# untitled.net
KiCad netlist of a schematic drawn in EAGLE
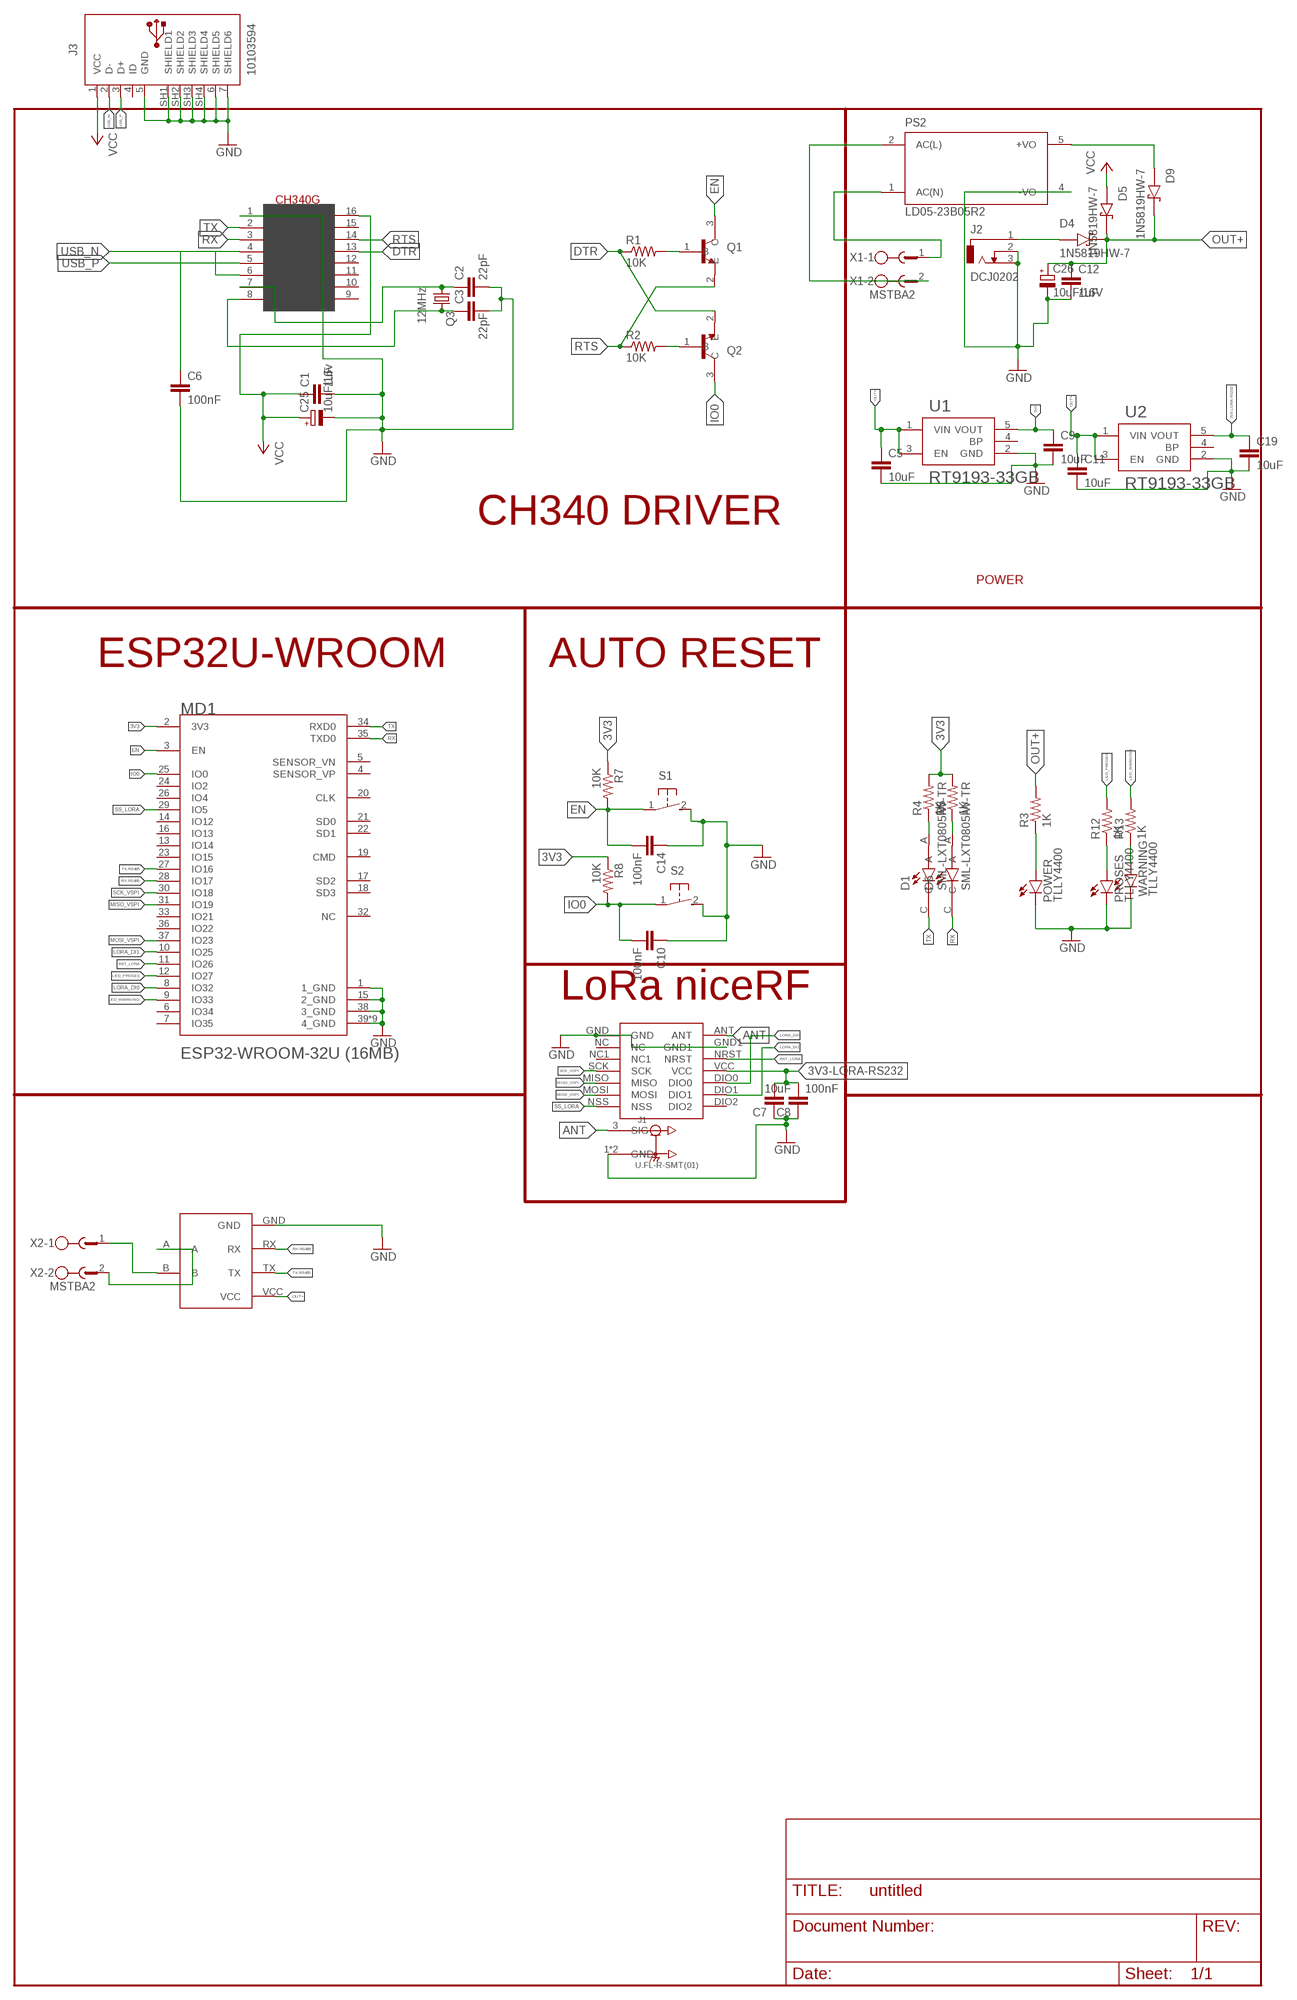
[diagram p0: schematic, sheet 1]

(export (version "E")
  (design (tool "Eeschema 10.0.6"))
  (components
    (comp (ref "C1")
      (value "1uF")
      (footprint "eagle-import:C0805K")
      (libsource (lib "eagle-import") (part "C-EUC0805K"))
    )
    (comp (ref "C2")
      (value "22pF")
      (footprint "eagle-import:C0805K")
      (libsource (lib "eagle-import") (part "C-EUC0805K"))
    )
    (comp (ref "C3")
      (value "22pF")
      (footprint "eagle-import:C0805K")
      (libsource (lib "eagle-import") (part "C-EUC0805K"))
    )
    (comp (ref "C5")
      (value "10uF")
      (footprint "eagle-import:C0805K")
      (libsource (lib "eagle-import") (part "C-EUC0805K"))
    )
    (comp (ref "C6")
      (value "100nF")
      (footprint "eagle-import:C0805K")
      (libsource (lib "eagle-import") (part "C-EUC0805K"))
    )
    (comp (ref "C7")
      (value "10uF")
      (footprint "eagle-import:C0805K")
      (libsource (lib "eagle-import") (part "C-EUC0805K"))
    )
    (comp (ref "C8")
      (value "100nF")
      (footprint "eagle-import:C0805K")
      (libsource (lib "eagle-import") (part "C-EUC0805K"))
    )
    (comp (ref "C9")
      (value "10uF")
      (footprint "eagle-import:C0805K")
      (libsource (lib "eagle-import") (part "C-EUC0805K"))
    )
    (comp (ref "C10")
      (value "100nF")
      (footprint "eagle-import:C0805K")
      (libsource (lib "eagle-import") (part "C-EUC0805K"))
    )
    (comp (ref "C11")
      (value "10uF")
      (footprint "eagle-import:C0805K")
      (libsource (lib "eagle-import") (part "C-EUC0805K"))
    )
    (comp (ref "C12")
      (value "1uF")
      (footprint "eagle-import:C0805K")
      (libsource (lib "eagle-import") (part "C-EUC0805K"))
    )
    (comp (ref "C14")
      (value "100nF")
      (footprint "eagle-import:C0805K")
      (libsource (lib "eagle-import") (part "C-EUC0805K"))
    )
    (comp (ref "C19")
      (value "10uF")
      (footprint "eagle-import:C0805K")
      (libsource (lib "eagle-import") (part "C-EUC0805K"))
    )
    (comp (ref "C25")
      (value "10uF/16v")
      (footprint "eagle-import:153CLV-0505")
      (libsource (lib "eagle-import") (part "CPOL-EU153CLV-0505"))
    )
    (comp (ref "C26")
      (value "10uF/16V")
      (footprint "eagle-import:153CLV-0505")
      (libsource (lib "eagle-import") (part "CPOL-EU153CLV-0505"))
    )
    (comp (ref "D1")
      (value "SML-LXT0805IW-TR")
      (footprint "eagle-import:LEDC2012X120N")
      (fields (field (name "MF") "Lumex Opto/Components"))
      (libsource (lib "eagle-import") (part "SML-LXT0805IW-TR"))
    )
    (comp (ref "D4")
      (value "1N5819HW-7")
      (footprint "eagle-import:SOD3715X145N")
      (fields (field (name "MF") "Diodes Inc."))
      (libsource (lib "eagle-import") (part "1N5819HW-7"))
    )
    (comp (ref "D5")
      (value "1N5819HW-7")
      (footprint "eagle-import:SOD3715X145N")
      (fields (field (name "MF") "Diodes Inc."))
      (libsource (lib "eagle-import") (part "1N5819HW-7"))
    )
    (comp (ref "D6")
      (value "SML-LXT0805IW-TR")
      (footprint "eagle-import:LEDC2012X120N")
      (fields (field (name "MF") "Lumex Opto/Components"))
      (libsource (lib "eagle-import") (part "SML-LXT0805IW-TR"))
    )
    (comp (ref "D9")
      (value "1N5819HW-7")
      (footprint "eagle-import:SOD3715X145N")
      (fields (field (name "MF") "Diodes Inc."))
      (libsource (lib "eagle-import") (part "1N5819HW-7"))
    )
    (comp (ref "J1")
      (value "U.FL-R-SMT(01)")
      (footprint "eagle-import:HRS_U.FL-R-SMT(01)")
      (fields (field (name "MF") "Hirose"))
      (libsource (lib "eagle-import") (part "U.FL-R-SMT(01)"))
    )
    (comp (ref "J2")
      (value "DCJ0202")
      (footprint "eagle-import:DCJ0202")
      (libsource (lib "eagle-import") (part "DCJ0202"))
    )
    (comp (ref "J3")
      (value "10103594")
      (footprint "eagle-import:10103594")
      (fields (field (name "MANUFACTURER") "Amphenol ICC (FCI)") (field (name "MPN") "10103594-0001LF"))
      (libsource (lib "eagle-import") (part "10103594"))
    )
    (comp (ref "LORA-NICERF-V1")
      (value "LORA-NICERF-V2")
      (footprint "eagle-import:LORA-NICERF-V2")
      (libsource (lib "eagle-import") (part "LORA-NICERF-V2"))
    )
    (comp (ref "MD1")
      (value "ESPRESSIF_SYSTEMS_ESP32-WROOM-32U_16MBESPRESSIF_SYSTEMS_ESP32-WROOM-32U_16MB_0_0")
      (footprint "eagle-import:ESPRESSIF_SYSTEMS_ESP32-WROOM-32U_16MB_0")
      (fields
        (field (name "DIGIKEY_PART_NUMBER") "1904-1028-1-ND")
        (field (name "MF") "Espressif Systems")
        (field (name "MOUSER_PART_NUMBER") "356-ES32WROOM32U16MB")
      )
      (libsource (lib "eagle-import") (part "ESPRESSIF_SYSTEMS_ESP32-WROOM-32U_16MBESPRESSIF_SYSTEMS_ESP32-WROOM-32U_16MB_0_0"))
    )
    (comp (ref "POWER")
      (value "TLLY4400")
      (footprint "eagle-import:LED3MM")
      (fields (field (name "MF") "VISHAY SEMICONDUCTOR"))
      (libsource (lib "eagle-import") (part "TLLY4400"))
    )
    (comp (ref "PROSES")
      (value "TLLY4400")
      (footprint "eagle-import:LED3MM")
      (fields (field (name "MF") "VISHAY SEMICONDUCTOR"))
      (libsource (lib "eagle-import") (part "TLLY4400"))
    )
    (comp (ref "PS2")
      (value "LD05-23B05R2")
      (footprint "eagle-import:CONV_LD05-23B05R2")
      (fields (field (name "MF") "Mornsun America, LLC"))
      (libsource (lib "eagle-import") (part "LD05-23B05R2"))
    )
    (comp (ref "Q1")
      (value "MMBT3904")
      (footprint "eagle-import:SOT95P240X120-3N")
      (fields (field (name "MF") "STMicroelectronics"))
      (libsource (lib "eagle-import") (part "MMBT3904"))
    )
    (comp (ref "Q2")
      (value "MMBT3904")
      (footprint "eagle-import:SOT95P240X120-3N")
      (fields (field (name "MF") "STMicroelectronics"))
      (libsource (lib "eagle-import") (part "MMBT3904"))
    )
    (comp (ref "Q3")
      (value "12MHz")
      (footprint "eagle-import:SM49")
      (libsource (lib "eagle-import") (part "CRYSTALSM49"))
    )
    (comp (ref "R1")
      (value "10K")
      (footprint "eagle-import:M0805")
      (libsource (lib "eagle-import") (part "R-US_M0805"))
    )
    (comp (ref "R2")
      (value "10K")
      (footprint "eagle-import:M0805")
      (libsource (lib "eagle-import") (part "R-US_M0805"))
    )
    (comp (ref "R3")
      (value "1K")
      (footprint "eagle-import:M0805")
      (libsource (lib "eagle-import") (part "R-US_M0805"))
    )
    (comp (ref "R4")
      (value "1K")
      (footprint "eagle-import:M0805")
      (libsource (lib "eagle-import") (part "R-US_M0805"))
    )
    (comp (ref "R5")
      (value "1K")
      (footprint "eagle-import:M0805")
      (libsource (lib "eagle-import") (part "R-US_M0805"))
    )
    (comp (ref "R7")
      (value "10K")
      (footprint "eagle-import:M0805")
      (libsource (lib "eagle-import") (part "R-US_M0805"))
    )
    (comp (ref "R8")
      (value "10K")
      (footprint "eagle-import:M0805")
      (libsource (lib "eagle-import") (part "R-US_M0805"))
    )
    (comp (ref "R12")
      (value "1K")
      (footprint "eagle-import:M0805")
      (libsource (lib "eagle-import") (part "R-US_M0805"))
    )
    (comp (ref "R13")
      (value "1K")
      (footprint "eagle-import:M0805")
      (libsource (lib "eagle-import") (part "R-US_M0805"))
    )
    (comp (ref "S1")
      (value "31-XX")
      (footprint "eagle-import:B3F-31XX")
      (fields (field (name "MPN") "B3F-3100"))
      (libsource (lib "eagle-import") (part "31-XX"))
    )
    (comp (ref "S2")
      (value "31-XX")
      (footprint "eagle-import:B3F-31XX")
      (fields (field (name "MPN") "B3F-3100"))
      (libsource (lib "eagle-import") (part "31-XX"))
    )
    (comp (ref "TTL-RS1")
      (value "TTL-RS485")
      (footprint "eagle-import:TTL-RS485")
      (libsource (lib "eagle-import") (part "TTL-RS485"))
    )
    (comp (ref "U$2")
      (value "CH340G")
      (footprint "eagle-import:SOIC16")
      (libsource (lib "eagle-import") (part "CH340G"))
    )
    (comp (ref "U1")
      (value "RT9193-33GB")
      (footprint "eagle-import:SOT94P279X129-5N")
      (fields (field (name "MF") "Richtek USA Inc."))
      (libsource (lib "eagle-import") (part "RT9193-33GB"))
    )
    (comp (ref "U2")
      (value "RT9193-33GB")
      (footprint "eagle-import:SOT94P279X129-5N")
      (fields (field (name "MF") "Richtek USA Inc."))
      (libsource (lib "eagle-import") (part "RT9193-33GB"))
    )
    (comp (ref "WARNING")
      (value "TLLY4400")
      (footprint "eagle-import:LED3MM")
      (fields (field (name "MF") "VISHAY SEMICONDUCTOR"))
      (libsource (lib "eagle-import") (part "TLLY4400"))
    )
    (comp (ref "X1")
      (value "MSTBA2")
      (footprint "eagle-import:MSTBA2")
      (fields (field (name "MF") "FARNELL") (field (name "MPN") "1757242"))
      (libsource (lib "eagle-import") (part "MSTBA2"))
    )
    (comp (ref "X2")
      (value "MSTBA2")
      (footprint "eagle-import:MSTBA2")
      (fields (field (name "MF") "FARNELL") (field (name "MPN") "1757242"))
      (libsource (lib "eagle-import") (part "MSTBA2"))
    )
  )
  (nets
    (net (code "1") (name "3V3") (class "Default")
      (node (ref "C9") (pin "1") (pinfunction "1_1") (pintype "passive"))
      (node (ref "MD1") (pin "2") (pinfunction "3V3_2") (pintype "power_in"))
      (node (ref "R4") (pin "2") (pinfunction "2_2") (pintype "passive"))
      (node (ref "R5") (pin "2") (pinfunction "2_2") (pintype "passive"))
      (node (ref "R7") (pin "1") (pinfunction "1_1") (pintype "passive"))
      (node (ref "R8") (pin "1") (pinfunction "1_1") (pintype "passive"))
      (node (ref "U1") (pin "5") (pinfunction "VOUT_5") (pintype "output"))
    )
    (net (code "2") (name "3V3-LORA-RS232") (class "Default")
      (node (ref "C19") (pin "1") (pinfunction "1_1") (pintype "passive"))
      (node (ref "C7") (pin "2") (pinfunction "2_2") (pintype "passive"))
      (node (ref "C8") (pin "2") (pinfunction "2_2") (pintype "passive"))
      (node (ref "LORA-NICERF-V1") (pin "VCC") (pinfunction "VCC_VCC") (pintype "bidirectional"))
      (node (ref "U2") (pin "5") (pinfunction "VOUT_5") (pintype "output"))
    )
    (net (code "3") (name "ANT") (class "Default")
      (node (ref "J1") (pin "3") (pinfunction "SIG_3") (pintype "passive"))
      (node (ref "LORA-NICERF-V1") (pin "ANT") (pinfunction "ANT_ANT") (pintype "bidirectional"))
    )
    (net (code "4") (name "DTR") (class "Default")
      (node (ref "Q2") (pin "2") (pinfunction "E_2") (pintype "passive"))
      (node (ref "R1") (pin "1") (pinfunction "1_1") (pintype "passive"))
      (node (ref "U$2") (pin "13") (pinfunction "DTR_13") (pintype "bidirectional"))
    )
    (net (code "5") (name "EN") (class "Default")
      (node (ref "C14") (pin "2") (pinfunction "2_2") (pintype "passive"))
      (node (ref "MD1") (pin "3") (pinfunction "EN_3") (pintype "input"))
      (node (ref "Q1") (pin "3") (pinfunction "C_3") (pintype "passive"))
      (node (ref "R7") (pin "2") (pinfunction "2_2") (pintype "passive"))
      (node (ref "S1") (pin "1") (pinfunction "P_1") (pintype "passive"))
    )
    (net (code "6") (name "GND") (class "Default")
      (node (ref "C1") (pin "2") (pinfunction "2_2") (pintype "passive"))
      (node (ref "C10") (pin "1") (pinfunction "1_1") (pintype "passive"))
      (node (ref "C11") (pin "2") (pinfunction "2_2") (pintype "passive"))
      (node (ref "C12") (pin "2") (pinfunction "2_2") (pintype "passive"))
      (node (ref "C14") (pin "1") (pinfunction "1_1") (pintype "passive"))
      (node (ref "C19") (pin "2") (pinfunction "2_2") (pintype "passive"))
      (node (ref "C2") (pin "2") (pinfunction "2_2") (pintype "passive"))
      (node (ref "C25") (pin "-") (pinfunction "-_-") (pintype "passive"))
      (node (ref "C26") (pin "-") (pinfunction "-_-") (pintype "passive"))
      (node (ref "C3") (pin "2") (pinfunction "2_2") (pintype "passive"))
      (node (ref "C5") (pin "2") (pinfunction "2_2") (pintype "passive"))
      (node (ref "C6") (pin "2") (pinfunction "2_2") (pintype "passive"))
      (node (ref "C7") (pin "1") (pinfunction "1_1") (pintype "passive"))
      (node (ref "C8") (pin "1") (pinfunction "1_1") (pintype "passive"))
      (node (ref "C9") (pin "2") (pinfunction "2_2") (pintype "passive"))
      (node (ref "J1") (pin "1") (pinfunction "GND_1") (pintype "passive"))
      (node (ref "J1") (pin "2") (pinfunction "GND_2") (pintype "passive"))
      (node (ref "J2") (pin "2") (pinfunction "2_2") (pintype "passive"))
      (node (ref "J2") (pin "3") (pinfunction "3_3") (pintype "passive"))
      (node (ref "J3") (pin "5") (pinfunction "GND_5") (pintype "power_in"))
      (node (ref "J3") (pin "6") (pinfunction "SHIELD5_6") (pintype "power_in"))
      (node (ref "J3") (pin "7") (pinfunction "SHIELD6_7") (pintype "power_in"))
      (node (ref "J3") (pin "SH1") (pinfunction "SHIELD1_SH1") (pintype "power_in"))
      (node (ref "J3") (pin "SH2") (pinfunction "SHIELD2_SH2") (pintype "power_in"))
      (node (ref "J3") (pin "SH3") (pinfunction "SHIELD3_SH3") (pintype "power_in"))
      (node (ref "J3") (pin "SH4") (pinfunction "SHIELD4_SH4") (pintype "power_in"))
      (node (ref "LORA-NICERF-V1") (pin "GND") (pinfunction "GND_GND") (pintype "bidirectional"))
      (node (ref "LORA-NICERF-V1") (pin "GND1") (pinfunction "GND1_GND1") (pintype "bidirectional"))
      (node (ref "MD1") (pin "1") (pinfunction "1_GND_1") (pintype "power_in"))
      (node (ref "MD1") (pin "15") (pinfunction "2_GND_15") (pintype "power_in"))
      (node (ref "MD1") (pin "38") (pinfunction "3_GND_38") (pintype "power_in"))
      (node (ref "MD1") (pin "39") (pinfunction "4_GND_39") (pintype "power_in"))
      (node (ref "MD1") (pin "39-2") (pinfunction "4_GND_39-2") (pintype "power_in"))
      (node (ref "MD1") (pin "39-3") (pinfunction "4_GND_39-3") (pintype "power_in"))
      (node (ref "MD1") (pin "39-4") (pinfunction "4_GND_39-4") (pintype "power_in"))
      (node (ref "MD1") (pin "39-5") (pinfunction "4_GND_39-5") (pintype "power_in"))
      (node (ref "MD1") (pin "39-6") (pinfunction "4_GND_39-6") (pintype "power_in"))
      (node (ref "MD1") (pin "39-7") (pinfunction "4_GND_39-7") (pintype "power_in"))
      (node (ref "MD1") (pin "39-8") (pinfunction "4_GND_39-8") (pintype "power_in"))
      (node (ref "MD1") (pin "39-9") (pinfunction "4_GND_39-9") (pintype "power_in"))
      (node (ref "POWER") (pin "K") (pinfunction "C_K") (pintype "passive"))
      (node (ref "PROSES") (pin "K") (pinfunction "C_K") (pintype "passive"))
      (node (ref "PS2") (pin "4") (pinfunction "-VO_4") (pintype "output"))
      (node (ref "S1") (pin "2") (pinfunction "S_2") (pintype "passive"))
      (node (ref "S2") (pin "2") (pinfunction "S_2") (pintype "passive"))
      (node (ref "TTL-RS1") (pin "GND") (pinfunction "GND_GND") (pintype "bidirectional"))
      (node (ref "U$2") (pin "1") (pinfunction "GND_1") (pintype "bidirectional"))
      (node (ref "U1") (pin "2") (pinfunction "GND_2") (pintype "power_in"))
      (node (ref "U2") (pin "2") (pinfunction "GND_2") (pintype "power_in"))
      (node (ref "WARNING") (pin "K") (pinfunction "C_K") (pintype "passive"))
    )
    (net (code "7") (name "IO0") (class "Default")
      (node (ref "C10") (pin "2") (pinfunction "2_2") (pintype "passive"))
      (node (ref "MD1") (pin "25") (pinfunction "IO0_25") (pintype "bidirectional"))
      (node (ref "Q2") (pin "3") (pinfunction "C_3") (pintype "passive"))
      (node (ref "R8") (pin "2") (pinfunction "2_2") (pintype "passive"))
      (node (ref "S2") (pin "1") (pinfunction "P_1") (pintype "passive"))
    )
    (net (code "8") (name "LED_PROSES") (class "Default")
      (node (ref "MD1") (pin "12") (pinfunction "IO27_12") (pintype "bidirectional"))
      (node (ref "R12") (pin "2") (pinfunction "2_2") (pintype "passive"))
    )
    (net (code "9") (name "LED_WARNING") (class "Default")
      (node (ref "MD1") (pin "9") (pinfunction "IO33_9") (pintype "bidirectional"))
      (node (ref "R13") (pin "2") (pinfunction "2_2") (pintype "passive"))
    )
    (net (code "10") (name "LORA_DI0") (class "Default")
      (node (ref "LORA-NICERF-V1") (pin "DIO0") (pinfunction "DIO0_DIO0") (pintype "bidirectional"))
      (node (ref "MD1") (pin "8") (pinfunction "IO32_8") (pintype "bidirectional"))
    )
    (net (code "11") (name "LORA_DI1") (class "Default")
      (node (ref "LORA-NICERF-V1") (pin "DIO1") (pinfunction "DIO1_DIO1") (pintype "bidirectional"))
      (node (ref "MD1") (pin "10") (pinfunction "IO25_10") (pintype "bidirectional"))
    )
    (net (code "12") (name "MISO_VSPI") (class "Default")
      (node (ref "LORA-NICERF-V1") (pin "MISO") (pinfunction "MISO_MISO") (pintype "bidirectional"))
      (node (ref "MD1") (pin "31") (pinfunction "IO19_31") (pintype "bidirectional"))
    )
    (net (code "13") (name "MOSI_VSPI") (class "Default")
      (node (ref "LORA-NICERF-V1") (pin "MOSI") (pinfunction "MOSI_MOSI") (pintype "bidirectional"))
      (node (ref "MD1") (pin "37") (pinfunction "IO23_37") (pintype "bidirectional"))
    )
    (net (code "14") (name "Net-(D1-PadA)") (class "Default")
      (node (ref "D1") (pin "A") (pinfunction "A_A") (pintype "passive"))
      (node (ref "R4") (pin "1") (pinfunction "1_1") (pintype "passive"))
    )
    (net (code "15") (name "Net-(D4-PadA)") (class "Default")
      (node (ref "D4") (pin "A") (pinfunction "A_A") (pintype "passive"))
      (node (ref "J2") (pin "1") (pinfunction "1_1") (pintype "passive"))
    )
    (net (code "16") (name "Net-(D6-PadA)") (class "Default")
      (node (ref "D6") (pin "A") (pinfunction "A_A") (pintype "passive"))
      (node (ref "R5") (pin "1") (pinfunction "1_1") (pintype "passive"))
    )
    (net (code "17") (name "Net-(POWER-PadA)") (class "Default")
      (node (ref "POWER") (pin "A") (pinfunction "A_A") (pintype "passive"))
      (node (ref "R3") (pin "1") (pinfunction "1_1") (pintype "passive"))
    )
    (net (code "18") (name "Net-(PROSES-PadA)") (class "Default")
      (node (ref "PROSES") (pin "A") (pinfunction "A_A") (pintype "passive"))
      (node (ref "R12") (pin "1") (pinfunction "1_1") (pintype "passive"))
    )
    (net (code "19") (name "Net-(PS2-+VO)") (class "Default")
      (node (ref "D9") (pin "A") (pinfunction "A_A") (pintype "passive"))
      (node (ref "PS2") (pin "5") (pinfunction "+VO_5") (pintype "output"))
    )
    (net (code "20") (name "Net-(PS2-AC(L))") (class "Default")
      (node (ref "PS2") (pin "2") (pinfunction "AC(L)_2") (pintype "input"))
      (node (ref "X1") (pin "2") (pinfunction "1_2") (pintype "passive"))
    )
    (net (code "21") (name "Net-(PS2-AC(N))") (class "Default")
      (node (ref "PS2") (pin "1") (pinfunction "AC(N)_1") (pintype "input"))
      (node (ref "X1") (pin "1") (pinfunction "1_1") (pintype "passive"))
    )
    (net (code "22") (name "Net-(Q1-B)") (class "Default")
      (node (ref "Q1") (pin "1") (pinfunction "B_1") (pintype "passive"))
      (node (ref "R1") (pin "2") (pinfunction "2_2") (pintype "passive"))
    )
    (net (code "23") (name "Net-(Q2-B)") (class "Default")
      (node (ref "Q2") (pin "1") (pinfunction "B_1") (pintype "passive"))
      (node (ref "R2") (pin "2") (pinfunction "2_2") (pintype "passive"))
    )
    (net (code "24") (name "Net-(R13-Pad1)") (class "Default")
      (node (ref "R13") (pin "1") (pinfunction "1_1") (pintype "passive"))
      (node (ref "WARNING") (pin "A") (pinfunction "A_A") (pintype "passive"))
    )
    (net (code "25") (name "Net-(TTL-RS1-PadB)") (class "Default")
      (node (ref "TTL-RS1") (pin "B") (pinfunction "B_B") (pintype "bidirectional"))
      (node (ref "X2") (pin "1") (pinfunction "1_1") (pintype "passive"))
    )
    (net (code "26") (name "Net-(U$2-V3)") (class "Default")
      (node (ref "C6") (pin "1") (pinfunction "1_1") (pintype "passive"))
      (node (ref "U$2") (pin "4") (pinfunction "V3_4") (pintype "bidirectional"))
    )
    (net (code "27") (name "Net-(U$2-XI)") (class "Default")
      (node (ref "C2") (pin "1") (pinfunction "1_1") (pintype "passive"))
      (node (ref "Q3") (pin "1") (pinfunction "1_1") (pintype "passive"))
      (node (ref "U$2") (pin "7") (pinfunction "XI_7") (pintype "bidirectional"))
    )
    (net (code "28") (name "Net-(U$2-XO)") (class "Default")
      (node (ref "C3") (pin "1") (pinfunction "1_1") (pintype "passive"))
      (node (ref "Q3") (pin "2") (pinfunction "2_2") (pintype "passive"))
      (node (ref "U$2") (pin "8") (pinfunction "XO_8") (pintype "bidirectional"))
    )
    (net (code "29") (name "Net-(X2B-1)") (class "Default")
      (node (ref "TTL-RS1") (pin "A") (pinfunction "A_A") (pintype "bidirectional"))
      (node (ref "X2") (pin "2") (pinfunction "1_2") (pintype "passive"))
    )
    (net (code "30") (name "OUT+") (class "Default")
      (node (ref "C11") (pin "1") (pinfunction "1_1") (pintype "passive"))
      (node (ref "C12") (pin "1") (pinfunction "1_1") (pintype "passive"))
      (node (ref "C26") (pin "+") (pinfunction "+_+") (pintype "passive"))
      (node (ref "C5") (pin "1") (pinfunction "1_1") (pintype "passive"))
      (node (ref "D4") (pin "C") (pinfunction "K_C") (pintype "passive"))
      (node (ref "D5") (pin "C") (pinfunction "K_C") (pintype "passive"))
      (node (ref "D9") (pin "C") (pinfunction "K_C") (pintype "passive"))
      (node (ref "R3") (pin "2") (pinfunction "2_2") (pintype "passive"))
      (node (ref "TTL-RS1") (pin "VCC") (pinfunction "VCC_VCC") (pintype "bidirectional"))
      (node (ref "U1") (pin "1") (pinfunction "VIN_1") (pintype "input"))
      (node (ref "U1") (pin "3") (pinfunction "EN_3") (pintype "input"))
      (node (ref "U2") (pin "1") (pinfunction "VIN_1") (pintype "input"))
      (node (ref "U2") (pin "3") (pinfunction "EN_3") (pintype "input"))
    )
    (net (code "31") (name "RST_LORA") (class "Default")
      (node (ref "LORA-NICERF-V1") (pin "NRST") (pinfunction "NRST_NRST") (pintype "bidirectional"))
      (node (ref "MD1") (pin "11") (pinfunction "IO26_11") (pintype "bidirectional"))
    )
    (net (code "32") (name "RTS") (class "Default")
      (node (ref "Q1") (pin "2") (pinfunction "E_2") (pintype "passive"))
      (node (ref "R2") (pin "1") (pinfunction "1_1") (pintype "passive"))
      (node (ref "U$2") (pin "14") (pinfunction "RTS_14") (pintype "bidirectional"))
    )
    (net (code "33") (name "RX") (class "Default")
      (node (ref "D6") (pin "C") (pinfunction "C_C") (pintype "passive"))
      (node (ref "MD1") (pin "35") (pinfunction "TXD0_35") (pintype "bidirectional"))
      (node (ref "U$2") (pin "3") (pinfunction "RX_3") (pintype "bidirectional"))
    )
    (net (code "34") (name "RX-RS485") (class "Default")
      (node (ref "MD1") (pin "28") (pinfunction "IO17_28") (pintype "bidirectional"))
      (node (ref "TTL-RS1") (pin "RX") (pinfunction "RX_RX") (pintype "bidirectional"))
    )
    (net (code "35") (name "SCK_VSPI") (class "Default")
      (node (ref "LORA-NICERF-V1") (pin "SCK") (pinfunction "SCK_SCK") (pintype "bidirectional"))
      (node (ref "MD1") (pin "30") (pinfunction "IO18_30") (pintype "bidirectional"))
    )
    (net (code "36") (name "SS_LORA") (class "Default")
      (node (ref "LORA-NICERF-V1") (pin "NSS") (pinfunction "NSS_NSS") (pintype "bidirectional"))
      (node (ref "MD1") (pin "29") (pinfunction "IO5_29") (pintype "bidirectional"))
    )
    (net (code "37") (name "TX") (class "Default")
      (node (ref "D1") (pin "C") (pinfunction "C_C") (pintype "passive"))
      (node (ref "MD1") (pin "34") (pinfunction "RXD0_34") (pintype "bidirectional"))
      (node (ref "U$2") (pin "2") (pinfunction "TX_2") (pintype "bidirectional"))
    )
    (net (code "38") (name "TX-RS485") (class "Default")
      (node (ref "MD1") (pin "27") (pinfunction "IO16_27") (pintype "bidirectional"))
      (node (ref "TTL-RS1") (pin "TX") (pinfunction "TX_TX") (pintype "bidirectional"))
    )
    (net (code "39") (name "USB_N") (class "Default")
      (node (ref "J3") (pin "2") (pinfunction "D-_2") (pintype "bidirectional"))
      (node (ref "U$2") (pin "6") (pinfunction "D-_6") (pintype "bidirectional"))
    )
    (net (code "40") (name "USB_P") (class "Default")
      (node (ref "J3") (pin "3") (pinfunction "D+_3") (pintype "bidirectional"))
      (node (ref "U$2") (pin "5") (pinfunction "D+_5") (pintype "bidirectional"))
    )
    (net (code "41") (name "VCC") (class "Default")
      (node (ref "C1") (pin "1") (pinfunction "1_1") (pintype "passive"))
      (node (ref "C25") (pin "+") (pinfunction "+_+") (pintype "passive"))
      (node (ref "D5") (pin "A") (pinfunction "A_A") (pintype "passive"))
      (node (ref "J3") (pin "1") (pinfunction "VCC_1") (pintype "power_in"))
      (node (ref "U$2") (pin "16") (pinfunction "VCC_16") (pintype "bidirectional"))
    )
    (net (code "42") (name "unconnected-(J3-ID-Pad4)") (class "Default")
      (node (ref "J3") (pin "4") (pinfunction "ID_4") (pintype "bidirectional"))
    )
    (net (code "43") (name "unconnected-(LORA-NICERF-V1-PadDIO2)") (class "Default")
      (node (ref "LORA-NICERF-V1") (pin "DIO2") (pinfunction "DIO2_DIO2") (pintype "bidirectional"))
    )
    (net (code "44") (name "unconnected-(LORA-NICERF-V1-PadNC)") (class "Default")
      (node (ref "LORA-NICERF-V1") (pin "NC") (pinfunction "NC_NC") (pintype "bidirectional"))
    )
    (net (code "45") (name "unconnected-(LORA-NICERF-V1-PadNC1)") (class "Default")
      (node (ref "LORA-NICERF-V1") (pin "NC1") (pinfunction "NC1_NC1") (pintype "bidirectional"))
    )
    (net (code "46") (name "unconnected-(MD1-CLK-Pad20)") (class "Default")
      (node (ref "MD1") (pin "20") (pinfunction "CLK_20") (pintype "bidirectional"))
    )
    (net (code "47") (name "unconnected-(MD1-CMD-Pad19)") (class "Default")
      (node (ref "MD1") (pin "19") (pinfunction "CMD_19") (pintype "bidirectional"))
    )
    (net (code "48") (name "unconnected-(MD1-IO2-Pad24)") (class "Default")
      (node (ref "MD1") (pin "24") (pinfunction "IO2_24") (pintype "bidirectional"))
    )
    (net (code "49") (name "unconnected-(MD1-IO4-Pad26)") (class "Default")
      (node (ref "MD1") (pin "26") (pinfunction "IO4_26") (pintype "bidirectional"))
    )
    (net (code "50") (name "unconnected-(MD1-IO12-Pad14)") (class "Default")
      (node (ref "MD1") (pin "14") (pinfunction "IO12_14") (pintype "bidirectional"))
    )
    (net (code "51") (name "unconnected-(MD1-IO13-Pad16)") (class "Default")
      (node (ref "MD1") (pin "16") (pinfunction "IO13_16") (pintype "bidirectional"))
    )
    (net (code "52") (name "unconnected-(MD1-IO14-Pad13)") (class "Default")
      (node (ref "MD1") (pin "13") (pinfunction "IO14_13") (pintype "bidirectional"))
    )
    (net (code "53") (name "unconnected-(MD1-IO15-Pad23)") (class "Default")
      (node (ref "MD1") (pin "23") (pinfunction "IO15_23") (pintype "bidirectional"))
    )
    (net (code "54") (name "unconnected-(MD1-IO21-Pad33)") (class "Default")
      (node (ref "MD1") (pin "33") (pinfunction "IO21_33") (pintype "bidirectional"))
    )
    (net (code "55") (name "unconnected-(MD1-IO22-Pad36)") (class "Default")
      (node (ref "MD1") (pin "36") (pinfunction "IO22_36") (pintype "bidirectional"))
    )
    (net (code "56") (name "unconnected-(MD1-IO34-Pad6)") (class "Default")
      (node (ref "MD1") (pin "6") (pinfunction "IO34_6") (pintype "bidirectional"))
    )
    (net (code "57") (name "unconnected-(MD1-IO35-Pad7)") (class "Default")
      (node (ref "MD1") (pin "7") (pinfunction "IO35_7") (pintype "bidirectional"))
    )
    (net (code "58") (name "unconnected-(MD1-NC-Pad32)") (class "Default")
      (node (ref "MD1") (pin "32") (pinfunction "NC_32") (pintype "passive"))
    )
    (net (code "59") (name "unconnected-(MD1-SD0-Pad21)") (class "Default")
      (node (ref "MD1") (pin "21") (pinfunction "SD0_21") (pintype "bidirectional"))
    )
    (net (code "60") (name "unconnected-(MD1-SD1-Pad22)") (class "Default")
      (node (ref "MD1") (pin "22") (pinfunction "SD1_22") (pintype "bidirectional"))
    )
    (net (code "61") (name "unconnected-(MD1-SD2-Pad17)") (class "Default")
      (node (ref "MD1") (pin "17") (pinfunction "SD2_17") (pintype "bidirectional"))
    )
    (net (code "62") (name "unconnected-(MD1-SD3-Pad18)") (class "Default")
      (node (ref "MD1") (pin "18") (pinfunction "SD3_18") (pintype "bidirectional"))
    )
    (net (code "63") (name "unconnected-(MD1-SENSOR_VN-Pad5)") (class "Default")
      (node (ref "MD1") (pin "5") (pinfunction "SENSOR_VN_5") (pintype "input"))
    )
    (net (code "64") (name "unconnected-(MD1-SENSOR_VP-Pad4)") (class "Default")
      (node (ref "MD1") (pin "4") (pinfunction "SENSOR_VP_4") (pintype "input"))
    )
    (net (code "65") (name "unconnected-(U$2-CTS-Pad9)") (class "Default")
      (node (ref "U$2") (pin "9") (pinfunction "CTS_9") (pintype "bidirectional"))
    )
    (net (code "66") (name "unconnected-(U$2-DCD-Pad12)") (class "Default")
      (node (ref "U$2") (pin "12") (pinfunction "DCD_12") (pintype "bidirectional"))
    )
    (net (code "67") (name "unconnected-(U$2-DSR-Pad10)") (class "Default")
      (node (ref "U$2") (pin "10") (pinfunction "DSR_10") (pintype "bidirectional"))
    )
    (net (code "68") (name "unconnected-(U$2-RI-Pad11)") (class "Default")
      (node (ref "U$2") (pin "11") (pinfunction "RI_11") (pintype "bidirectional"))
    )
    (net (code "69") (name "unconnected-(U$2-RS232-Pad15)") (class "Default")
      (node (ref "U$2") (pin "15") (pinfunction "RS232_15") (pintype "bidirectional"))
    )
    (net (code "70") (name "unconnected-(U1-BP-Pad4)") (class "Default")
      (node (ref "U1") (pin "4") (pinfunction "BP_4") (pintype "passive"))
    )
    (net (code "71") (name "unconnected-(U2-BP-Pad4)") (class "Default")
      (node (ref "U2") (pin "4") (pinfunction "BP_4") (pintype "passive"))
    )
  )
)
